# Printing3.net
KiCad netlist of a schematic drawn in Altium Designer
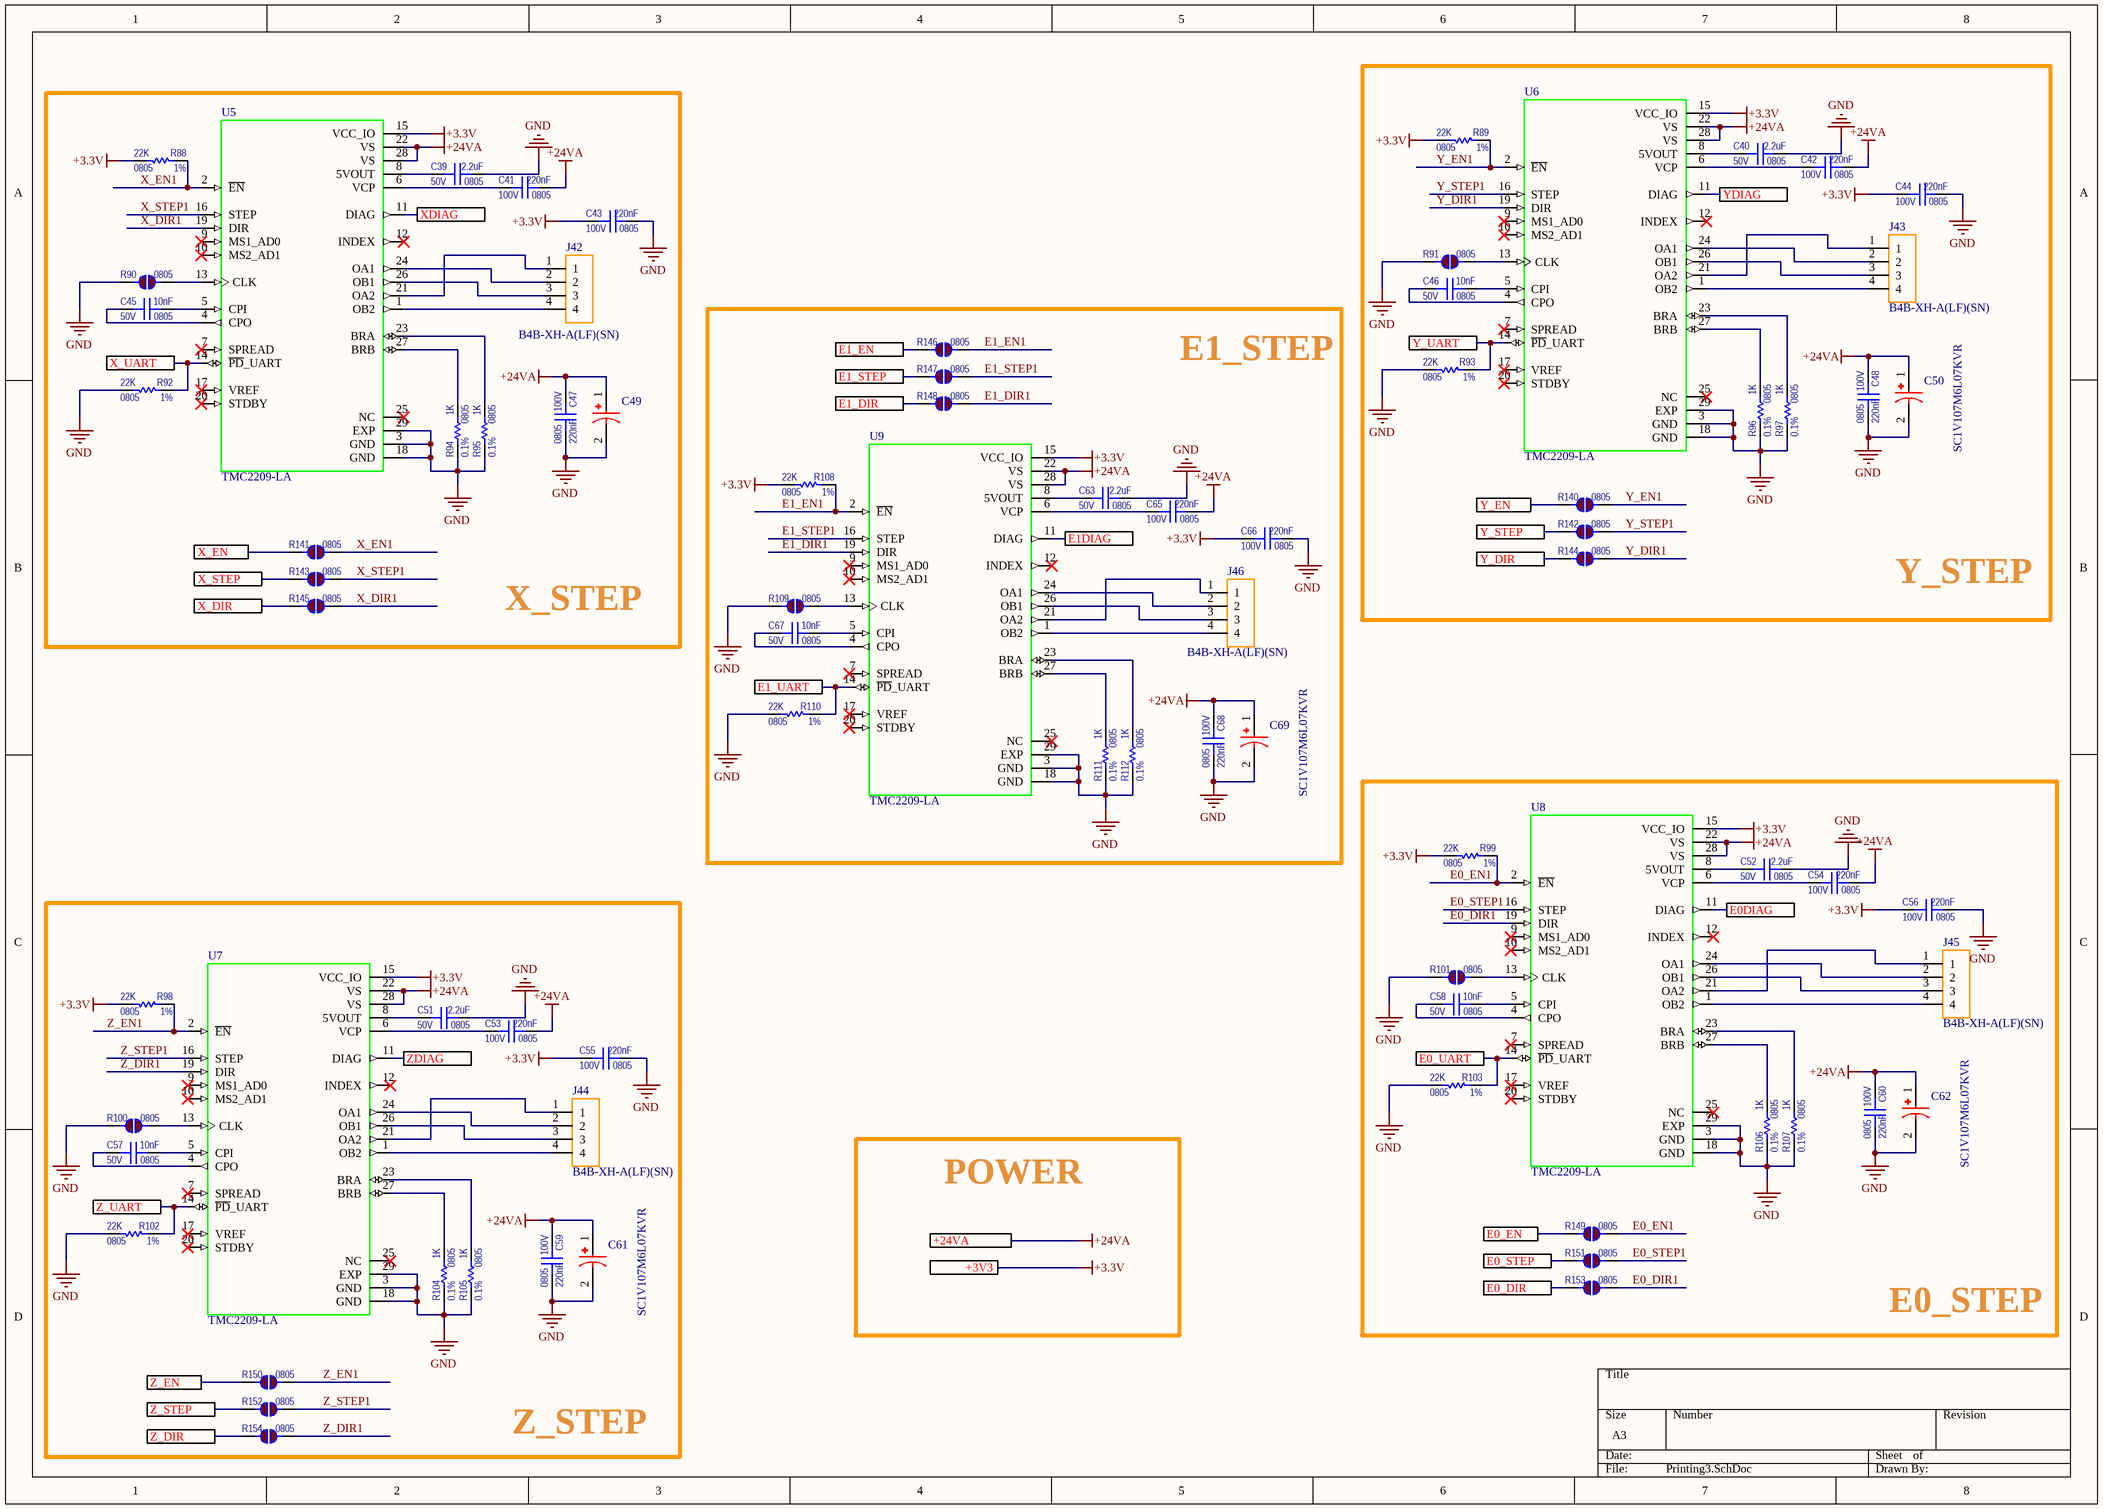
[diagram p0: Printing3.SchDoc]

(export (version "E")
  (design (tool "Eeschema 10.0.6"))
  (components
    (comp (ref "C39")
      (value "2.2uF")
      (footprint "C_0805_GEN_1.40H")
      (description "CAP_CER_2.2uF_16V_X7R_10%_0805")
      (fields
        (field (name "VOLTAGE") "50V")
        (field (name "PACKAGE") "0805")
        (field (name "SIMILAR PART") "CGA4J3X7R1C225K125AB")
        (field (name "TOLERANCE") "10%")
        (field (name "ADDED BY") "SonerI")
        (field (name "CHECKED BY") "İlkerU")
      )
      (libsource (lib "FireANTs_HwLibDB") (part "Capacitor"))
    )
    (comp (ref "C40")
      (value "2.2uF")
      (footprint "C_0805_GEN_1.40H")
      (description "CAP_CER_2.2uF_16V_X7R_10%_0805")
      (fields
        (field (name "VOLTAGE") "50V")
        (field (name "PACKAGE") "0805")
        (field (name "SIMILAR PART") "CGA4J3X7R1C225K125AB")
        (field (name "TOLERANCE") "10%")
        (field (name "ADDED BY") "SonerI")
        (field (name "CHECKED BY") "İlkerU")
      )
      (libsource (lib "FireANTs_HwLibDB") (part "Capacitor"))
    )
    (comp (ref "C41")
      (value "220nF")
      (footprint "C_0805_GEN_1.40H")
      (description "CAP_CER_220nF_100V_X7R_10%_0805")
      (fields
        (field (name "VOLTAGE") "100V")
        (field (name "PACKAGE") "0805")
        (field (name "SIMILAR PART") "CC0805KKX7R0BB224; GRM21AR72A224KAC5L")
        (field (name "TOLERANCE") "10%")
        (field (name "ADDED BY") "YasinY")
        (field (name "CHECKED BY") "İlkerU")
      )
      (libsource (lib "FireANTs_HwLibDB") (part "Capacitor"))
    )
    (comp (ref "C42")
      (value "220nF")
      (footprint "C_0805_GEN_1.40H")
      (description "CAP_CER_220nF_100V_X7R_10%_0805")
      (fields
        (field (name "VOLTAGE") "100V")
        (field (name "PACKAGE") "0805")
        (field (name "SIMILAR PART") "CC0805KKX7R0BB224; GRM21AR72A224KAC5L")
        (field (name "TOLERANCE") "10%")
        (field (name "ADDED BY") "YasinY")
        (field (name "CHECKED BY") "İlkerU")
      )
      (libsource (lib "FireANTs_HwLibDB") (part "Capacitor"))
    )
    (comp (ref "C43")
      (value "220nF")
      (footprint "C_0805_GEN_1.40H")
      (description "CAP_CER_220nF_100V_X7R_10%_0805")
      (fields
        (field (name "VOLTAGE") "100V")
        (field (name "PACKAGE") "0805")
        (field (name "SIMILAR PART") "CC0805KKX7R0BB224; GRM21AR72A224KAC5L")
        (field (name "TOLERANCE") "10%")
        (field (name "ADDED BY") "YasinY")
        (field (name "CHECKED BY") "İlkerU")
      )
      (libsource (lib "FireANTs_HwLibDB") (part "Capacitor"))
    )
    (comp (ref "C44")
      (value "220nF")
      (footprint "C_0805_GEN_1.40H")
      (description "CAP_CER_220nF_100V_X7R_10%_0805")
      (fields
        (field (name "VOLTAGE") "100V")
        (field (name "PACKAGE") "0805")
        (field (name "SIMILAR PART") "CC0805KKX7R0BB224; GRM21AR72A224KAC5L")
        (field (name "TOLERANCE") "10%")
        (field (name "ADDED BY") "YasinY")
        (field (name "CHECKED BY") "İlkerU")
      )
      (libsource (lib "FireANTs_HwLibDB") (part "Capacitor"))
    )
    (comp (ref "C45")
      (value "10nF")
      (footprint "C_0805_GEN_1.10H")
      (description "CAP_CER_10nF_50V_NP0_5%_0805")
      (fields
        (field (name "VOLTAGE") "50V")
        (field (name "PACKAGE") "0805")
        (field (name "SIMILAR PART") "CGA4C2C0G1H103J060AA")
        (field (name "TOLERANCE") "5%")
        (field (name "ADDED BY") "SonerI")
        (field (name "CHECKED BY") "İlkerU")
      )
      (libsource (lib "FireANTs_HwLibDB") (part "Capacitor"))
    )
    (comp (ref "C46")
      (value "10nF")
      (footprint "C_0805_GEN_1.10H")
      (description "CAP_CER_10nF_50V_NP0_5%_0805")
      (fields
        (field (name "VOLTAGE") "50V")
        (field (name "PACKAGE") "0805")
        (field (name "SIMILAR PART") "CGA4C2C0G1H103J060AA")
        (field (name "TOLERANCE") "5%")
        (field (name "ADDED BY") "SonerI")
        (field (name "CHECKED BY") "İlkerU")
      )
      (libsource (lib "FireANTs_HwLibDB") (part "Capacitor"))
    )
    (comp (ref "C47")
      (value "220nF")
      (footprint "C_0805_GEN_1.40H")
      (description "CAP_CER_220nF_100V_X7R_10%_0805")
      (fields
        (field (name "VOLTAGE") "100V")
        (field (name "PACKAGE") "0805")
        (field (name "SIMILAR PART") "CC0805KKX7R0BB224; GRM21AR72A224KAC5L")
        (field (name "TOLERANCE") "10%")
        (field (name "ADDED BY") "YasinY")
        (field (name "CHECKED BY") "İlkerU")
      )
      (libsource (lib "FireANTs_HwLibDB") (part "Capacitor"))
    )
    (comp (ref "C48")
      (value "220nF")
      (footprint "C_0805_GEN_1.40H")
      (description "CAP_CER_220nF_100V_X7R_10%_0805")
      (fields
        (field (name "VOLTAGE") "100V")
        (field (name "PACKAGE") "0805")
        (field (name "SIMILAR PART") "CC0805KKX7R0BB224; GRM21AR72A224KAC5L")
        (field (name "TOLERANCE") "10%")
        (field (name "ADDED BY") "YasinY")
        (field (name "CHECKED BY") "İlkerU")
      )
      (libsource (lib "FireANTs_HwLibDB") (part "Capacitor"))
    )
    (comp (ref "C49")
      (value "SC1V107M6L07KVR")
      (footprint "SC1V107M6L07KVR")
      (libsource (lib "Printing") (part "SC1V107M6L07KVR"))
    )
    (comp (ref "C50")
      (value "SC1V107M6L07KVR")
      (footprint "SC1V107M6L07KVR")
      (libsource (lib "Printing") (part "SC1V107M6L07KVR"))
    )
    (comp (ref "C51")
      (value "2.2uF")
      (footprint "C_0805_GEN_1.40H")
      (description "CAP_CER_2.2uF_16V_X7R_10%_0805")
      (fields
        (field (name "VOLTAGE") "50V")
        (field (name "PACKAGE") "0805")
        (field (name "SIMILAR PART") "CGA4J3X7R1C225K125AB")
        (field (name "TOLERANCE") "10%")
        (field (name "ADDED BY") "SonerI")
        (field (name "CHECKED BY") "İlkerU")
      )
      (libsource (lib "FireANTs_HwLibDB") (part "Capacitor"))
    )
    (comp (ref "C52")
      (value "2.2uF")
      (footprint "C_0805_GEN_1.40H")
      (description "CAP_CER_2.2uF_16V_X7R_10%_0805")
      (fields
        (field (name "VOLTAGE") "50V")
        (field (name "PACKAGE") "0805")
        (field (name "SIMILAR PART") "CGA4J3X7R1C225K125AB")
        (field (name "TOLERANCE") "10%")
        (field (name "ADDED BY") "SonerI")
        (field (name "CHECKED BY") "İlkerU")
      )
      (libsource (lib "FireANTs_HwLibDB") (part "Capacitor"))
    )
    (comp (ref "C53")
      (value "220nF")
      (footprint "C_0805_GEN_1.40H")
      (description "CAP_CER_220nF_100V_X7R_10%_0805")
      (fields
        (field (name "VOLTAGE") "100V")
        (field (name "PACKAGE") "0805")
        (field (name "SIMILAR PART") "CC0805KKX7R0BB224; GRM21AR72A224KAC5L")
        (field (name "TOLERANCE") "10%")
        (field (name "ADDED BY") "YasinY")
        (field (name "CHECKED BY") "İlkerU")
      )
      (libsource (lib "FireANTs_HwLibDB") (part "Capacitor"))
    )
    (comp (ref "C54")
      (value "220nF")
      (footprint "C_0805_GEN_1.40H")
      (description "CAP_CER_220nF_100V_X7R_10%_0805")
      (fields
        (field (name "VOLTAGE") "100V")
        (field (name "PACKAGE") "0805")
        (field (name "SIMILAR PART") "CC0805KKX7R0BB224; GRM21AR72A224KAC5L")
        (field (name "TOLERANCE") "10%")
        (field (name "ADDED BY") "YasinY")
        (field (name "CHECKED BY") "İlkerU")
      )
      (libsource (lib "FireANTs_HwLibDB") (part "Capacitor"))
    )
    (comp (ref "C55")
      (value "220nF")
      (footprint "C_0805_GEN_1.40H")
      (description "CAP_CER_220nF_100V_X7R_10%_0805")
      (fields
        (field (name "VOLTAGE") "100V")
        (field (name "PACKAGE") "0805")
        (field (name "SIMILAR PART") "CC0805KKX7R0BB224; GRM21AR72A224KAC5L")
        (field (name "TOLERANCE") "10%")
        (field (name "ADDED BY") "YasinY")
        (field (name "CHECKED BY") "İlkerU")
      )
      (libsource (lib "FireANTs_HwLibDB") (part "Capacitor"))
    )
    (comp (ref "C56")
      (value "220nF")
      (footprint "C_0805_GEN_1.40H")
      (description "CAP_CER_220nF_100V_X7R_10%_0805")
      (fields
        (field (name "VOLTAGE") "100V")
        (field (name "PACKAGE") "0805")
        (field (name "SIMILAR PART") "CC0805KKX7R0BB224; GRM21AR72A224KAC5L")
        (field (name "TOLERANCE") "10%")
        (field (name "ADDED BY") "YasinY")
        (field (name "CHECKED BY") "İlkerU")
      )
      (libsource (lib "FireANTs_HwLibDB") (part "Capacitor"))
    )
    (comp (ref "C57")
      (value "10nF")
      (footprint "C_0805_GEN_1.10H")
      (description "CAP_CER_10nF_50V_NP0_5%_0805")
      (fields
        (field (name "VOLTAGE") "50V")
        (field (name "PACKAGE") "0805")
        (field (name "SIMILAR PART") "CGA4C2C0G1H103J060AA")
        (field (name "TOLERANCE") "5%")
        (field (name "ADDED BY") "SonerI")
        (field (name "CHECKED BY") "İlkerU")
      )
      (libsource (lib "FireANTs_HwLibDB") (part "Capacitor"))
    )
    (comp (ref "C58")
      (value "10nF")
      (footprint "C_0805_GEN_1.10H")
      (description "CAP_CER_10nF_50V_NP0_5%_0805")
      (fields
        (field (name "VOLTAGE") "50V")
        (field (name "PACKAGE") "0805")
        (field (name "SIMILAR PART") "CGA4C2C0G1H103J060AA")
        (field (name "TOLERANCE") "5%")
        (field (name "ADDED BY") "SonerI")
        (field (name "CHECKED BY") "İlkerU")
      )
      (libsource (lib "FireANTs_HwLibDB") (part "Capacitor"))
    )
    (comp (ref "C59")
      (value "220nF")
      (footprint "C_0805_GEN_1.40H")
      (description "CAP_CER_220nF_100V_X7R_10%_0805")
      (fields
        (field (name "VOLTAGE") "100V")
        (field (name "PACKAGE") "0805")
        (field (name "SIMILAR PART") "CC0805KKX7R0BB224; GRM21AR72A224KAC5L")
        (field (name "TOLERANCE") "10%")
        (field (name "ADDED BY") "YasinY")
        (field (name "CHECKED BY") "İlkerU")
      )
      (libsource (lib "FireANTs_HwLibDB") (part "Capacitor"))
    )
    (comp (ref "C60")
      (value "220nF")
      (footprint "C_0805_GEN_1.40H")
      (description "CAP_CER_220nF_100V_X7R_10%_0805")
      (fields
        (field (name "VOLTAGE") "100V")
        (field (name "PACKAGE") "0805")
        (field (name "SIMILAR PART") "CC0805KKX7R0BB224; GRM21AR72A224KAC5L")
        (field (name "TOLERANCE") "10%")
        (field (name "ADDED BY") "YasinY")
        (field (name "CHECKED BY") "İlkerU")
      )
      (libsource (lib "FireANTs_HwLibDB") (part "Capacitor"))
    )
    (comp (ref "C61")
      (value "SC1V107M6L07KVR")
      (footprint "SC1V107M6L07KVR")
      (libsource (lib "Printing") (part "SC1V107M6L07KVR"))
    )
    (comp (ref "C62")
      (value "SC1V107M6L07KVR")
      (footprint "SC1V107M6L07KVR")
      (libsource (lib "Printing") (part "SC1V107M6L07KVR"))
    )
    (comp (ref "C63")
      (value "2.2uF")
      (footprint "C_0805_GEN_1.40H")
      (description "CAP_CER_2.2uF_16V_X7R_10%_0805")
      (fields
        (field (name "VOLTAGE") "50V")
        (field (name "PACKAGE") "0805")
        (field (name "SIMILAR PART") "CGA4J3X7R1C225K125AB")
        (field (name "TOLERANCE") "10%")
        (field (name "ADDED BY") "SonerI")
        (field (name "CHECKED BY") "İlkerU")
      )
      (libsource (lib "FireANTs_HwLibDB") (part "Capacitor"))
    )
    (comp (ref "C65")
      (value "220nF")
      (footprint "C_0805_GEN_1.40H")
      (description "CAP_CER_220nF_100V_X7R_10%_0805")
      (fields
        (field (name "VOLTAGE") "100V")
        (field (name "PACKAGE") "0805")
        (field (name "SIMILAR PART") "CC0805KKX7R0BB224; GRM21AR72A224KAC5L")
        (field (name "TOLERANCE") "10%")
        (field (name "ADDED BY") "YasinY")
        (field (name "CHECKED BY") "İlkerU")
      )
      (libsource (lib "FireANTs_HwLibDB") (part "Capacitor"))
    )
    (comp (ref "C66")
      (value "220nF")
      (footprint "C_0805_GEN_1.40H")
      (description "CAP_CER_220nF_100V_X7R_10%_0805")
      (fields
        (field (name "VOLTAGE") "100V")
        (field (name "PACKAGE") "0805")
        (field (name "SIMILAR PART") "CC0805KKX7R0BB224; GRM21AR72A224KAC5L")
        (field (name "TOLERANCE") "10%")
        (field (name "ADDED BY") "YasinY")
        (field (name "CHECKED BY") "İlkerU")
      )
      (libsource (lib "FireANTs_HwLibDB") (part "Capacitor"))
    )
    (comp (ref "C67")
      (value "10nF")
      (footprint "C_0805_GEN_1.10H")
      (description "CAP_CER_10nF_50V_NP0_5%_0805")
      (fields
        (field (name "VOLTAGE") "50V")
        (field (name "PACKAGE") "0805")
        (field (name "SIMILAR PART") "CGA4C2C0G1H103J060AA")
        (field (name "TOLERANCE") "5%")
        (field (name "ADDED BY") "SonerI")
        (field (name "CHECKED BY") "İlkerU")
      )
      (libsource (lib "FireANTs_HwLibDB") (part "Capacitor"))
    )
    (comp (ref "C68")
      (value "220nF")
      (footprint "C_0805_GEN_1.40H")
      (description "CAP_CER_220nF_100V_X7R_10%_0805")
      (fields
        (field (name "VOLTAGE") "100V")
        (field (name "PACKAGE") "0805")
        (field (name "SIMILAR PART") "CC0805KKX7R0BB224; GRM21AR72A224KAC5L")
        (field (name "TOLERANCE") "10%")
        (field (name "ADDED BY") "YasinY")
        (field (name "CHECKED BY") "İlkerU")
      )
      (libsource (lib "FireANTs_HwLibDB") (part "Capacitor"))
    )
    (comp (ref "C69")
      (value "SC1V107M6L07KVR")
      (footprint "SC1V107M6L07KVR")
      (libsource (lib "Printing") (part "SC1V107M6L07KVR"))
    )
    (comp (ref "J42")
      (value "B4B-XH-A(LF)(SN)")
      (footprint "JST_B4B-XH-A(LF)(SN)")
      (libsource (lib "Printing") (part "B4B-XH-A(LF)(SN)"))
    )
    (comp (ref "J43")
      (value "B4B-XH-A(LF)(SN)")
      (footprint "JST_B4B-XH-A(LF)(SN)")
      (libsource (lib "Printing") (part "B4B-XH-A(LF)(SN)"))
    )
    (comp (ref "J44")
      (value "B4B-XH-A(LF)(SN)")
      (footprint "JST_B4B-XH-A(LF)(SN)")
      (libsource (lib "Printing") (part "B4B-XH-A(LF)(SN)"))
    )
    (comp (ref "J45")
      (value "B4B-XH-A(LF)(SN)")
      (footprint "JST_B4B-XH-A(LF)(SN)")
      (libsource (lib "Printing") (part "B4B-XH-A(LF)(SN)"))
    )
    (comp (ref "J46")
      (value "B4B-XH-A(LF)(SN)")
      (footprint "JST_B4B-XH-A(LF)(SN)")
      (libsource (lib "Printing") (part "B4B-XH-A(LF)(SN)"))
    )
    (comp (ref "R88")
      (value "22K")
      (footprint "R_0805_GEN_0.70H")
      (description "RES_STD_22K_0.125W_1%_100ppm_0805")
      (fields
        (field (name "TOLERANCE") "1%")
        (field (name "PACKAGE") "0805")
        (field (name "VOLTAGE") "150V")
        (field (name "Comment") "StandardResistor")
        (field (name "ADDED BY") "SonerI")
        (field (name "CHECKED BY") "YasinY")
      )
      (libsource (lib "FireANTs_HwLibDB") (part "StandardResistor"))
    )
    (comp (ref "R89")
      (value "22K")
      (footprint "R_0805_GEN_0.70H")
      (description "RES_STD_22K_0.125W_1%_100ppm_0805")
      (fields
        (field (name "TOLERANCE") "1%")
        (field (name "PACKAGE") "0805")
        (field (name "VOLTAGE") "150V")
        (field (name "Comment") "StandardResistor")
        (field (name "ADDED BY") "SonerI")
        (field (name "CHECKED BY") "YasinY")
      )
      (libsource (lib "FireANTs_HwLibDB") (part "StandardResistor"))
    )
    (comp (ref "R90")
      (value "StandardJumper")
      (footprint "R_0805_GEN_0.70H")
      (description "RES_STD_0R_0.125W_0805")
      (fields
        (field (name "PACKAGE") "0805")
        (field (name "TOLERANCE") "5%")
        (field (name "VOLTAGE") "150V")
        (field (name "ADDED BY") "İlhanT")
        (field (name "CHECKED BY") "YasinY")
      )
      (libsource (lib "FireANTs_HwLibDB") (part "StandardJumper"))
    )
    (comp (ref "R91")
      (value "StandardJumper")
      (footprint "R_0805_GEN_0.70H")
      (description "RES_STD_0R_0.125W_0805")
      (fields
        (field (name "PACKAGE") "0805")
        (field (name "TOLERANCE") "5%")
        (field (name "VOLTAGE") "150V")
        (field (name "ADDED BY") "İlhanT")
        (field (name "CHECKED BY") "YasinY")
      )
      (libsource (lib "FireANTs_HwLibDB") (part "StandardJumper"))
    )
    (comp (ref "R92")
      (value "22K")
      (footprint "R_0805_GEN_0.70H")
      (description "RES_STD_22K_0.125W_1%_100ppm_0805")
      (fields
        (field (name "TOLERANCE") "1%")
        (field (name "PACKAGE") "0805")
        (field (name "VOLTAGE") "150V")
        (field (name "Comment") "StandardResistor")
        (field (name "ADDED BY") "SonerI")
        (field (name "CHECKED BY") "YasinY")
      )
      (libsource (lib "FireANTs_HwLibDB") (part "StandardResistor"))
    )
    (comp (ref "R93")
      (value "22K")
      (footprint "R_0805_GEN_0.70H")
      (description "RES_STD_22K_0.125W_1%_100ppm_0805")
      (fields
        (field (name "TOLERANCE") "1%")
        (field (name "PACKAGE") "0805")
        (field (name "VOLTAGE") "150V")
        (field (name "Comment") "StandardResistor")
        (field (name "ADDED BY") "SonerI")
        (field (name "CHECKED BY") "YasinY")
      )
      (libsource (lib "FireANTs_HwLibDB") (part "StandardResistor"))
    )
    (comp (ref "R94")
      (value "1K")
      (footprint "R_0805_GEN_0.70H")
      (description "RES_STD_1K_0.125W_0.1%_25ppm_0805")
      (fields
        (field (name "TOLERANCE") "0.1%")
        (field (name "PACKAGE") "0805")
        (field (name "SIMILAR PART") "RN73C2A1K0BTD")
        (field (name "VOLTAGE") "100V")
        (field (name "ADDED BY") "İlhanT")
        (field (name "CHECKED BY") "YasinY")
      )
      (libsource (lib "FireANTs_HwLibDB") (part "StandardResistor"))
    )
    (comp (ref "R95")
      (value "1K")
      (footprint "R_0805_GEN_0.70H")
      (description "RES_STD_1K_0.125W_0.1%_25ppm_0805")
      (fields
        (field (name "TOLERANCE") "0.1%")
        (field (name "PACKAGE") "0805")
        (field (name "SIMILAR PART") "RN73C2A1K0BTD")
        (field (name "VOLTAGE") "100V")
        (field (name "ADDED BY") "İlhanT")
        (field (name "CHECKED BY") "YasinY")
      )
      (libsource (lib "FireANTs_HwLibDB") (part "StandardResistor"))
    )
    (comp (ref "R96")
      (value "1K")
      (footprint "R_0805_GEN_0.70H")
      (description "RES_STD_1K_0.125W_0.1%_25ppm_0805")
      (fields
        (field (name "TOLERANCE") "0.1%")
        (field (name "PACKAGE") "0805")
        (field (name "SIMILAR PART") "RN73C2A1K0BTD")
        (field (name "VOLTAGE") "100V")
        (field (name "ADDED BY") "İlhanT")
        (field (name "CHECKED BY") "YasinY")
      )
      (libsource (lib "FireANTs_HwLibDB") (part "StandardResistor"))
    )
    (comp (ref "R97")
      (value "1K")
      (footprint "R_0805_GEN_0.70H")
      (description "RES_STD_1K_0.125W_0.1%_25ppm_0805")
      (fields
        (field (name "TOLERANCE") "0.1%")
        (field (name "PACKAGE") "0805")
        (field (name "SIMILAR PART") "RN73C2A1K0BTD")
        (field (name "VOLTAGE") "100V")
        (field (name "ADDED BY") "İlhanT")
        (field (name "CHECKED BY") "YasinY")
      )
      (libsource (lib "FireANTs_HwLibDB") (part "StandardResistor"))
    )
    (comp (ref "R98")
      (value "22K")
      (footprint "R_0805_GEN_0.70H")
      (description "RES_STD_22K_0.125W_1%_100ppm_0805")
      (fields
        (field (name "TOLERANCE") "1%")
        (field (name "PACKAGE") "0805")
        (field (name "VOLTAGE") "150V")
        (field (name "Comment") "StandardResistor")
        (field (name "ADDED BY") "SonerI")
        (field (name "CHECKED BY") "YasinY")
      )
      (libsource (lib "FireANTs_HwLibDB") (part "StandardResistor"))
    )
    (comp (ref "R99")
      (value "22K")
      (footprint "R_0805_GEN_0.70H")
      (description "RES_STD_22K_0.125W_1%_100ppm_0805")
      (fields
        (field (name "TOLERANCE") "1%")
        (field (name "PACKAGE") "0805")
        (field (name "VOLTAGE") "150V")
        (field (name "Comment") "StandardResistor")
        (field (name "ADDED BY") "SonerI")
        (field (name "CHECKED BY") "YasinY")
      )
      (libsource (lib "FireANTs_HwLibDB") (part "StandardResistor"))
    )
    (comp (ref "R100")
      (value "StandardJumper")
      (footprint "R_0805_GEN_0.70H")
      (description "RES_STD_0R_0.125W_0805")
      (fields
        (field (name "PACKAGE") "0805")
        (field (name "TOLERANCE") "5%")
        (field (name "VOLTAGE") "150V")
        (field (name "ADDED BY") "İlhanT")
        (field (name "CHECKED BY") "YasinY")
      )
      (libsource (lib "FireANTs_HwLibDB") (part "StandardJumper"))
    )
    (comp (ref "R101")
      (value "StandardJumper")
      (footprint "R_0805_GEN_0.70H")
      (description "RES_STD_0R_0.125W_0805")
      (fields
        (field (name "PACKAGE") "0805")
        (field (name "TOLERANCE") "5%")
        (field (name "VOLTAGE") "150V")
        (field (name "ADDED BY") "İlhanT")
        (field (name "CHECKED BY") "YasinY")
      )
      (libsource (lib "FireANTs_HwLibDB") (part "StandardJumper"))
    )
    (comp (ref "R102")
      (value "22K")
      (footprint "R_0805_GEN_0.70H")
      (description "RES_STD_22K_0.125W_1%_100ppm_0805")
      (fields
        (field (name "TOLERANCE") "1%")
        (field (name "PACKAGE") "0805")
        (field (name "VOLTAGE") "150V")
        (field (name "Comment") "StandardResistor")
        (field (name "ADDED BY") "SonerI")
        (field (name "CHECKED BY") "YasinY")
      )
      (libsource (lib "FireANTs_HwLibDB") (part "StandardResistor"))
    )
    (comp (ref "R103")
      (value "22K")
      (footprint "R_0805_GEN_0.70H")
      (description "RES_STD_22K_0.125W_1%_100ppm_0805")
      (fields
        (field (name "TOLERANCE") "1%")
        (field (name "PACKAGE") "0805")
        (field (name "VOLTAGE") "150V")
        (field (name "Comment") "StandardResistor")
        (field (name "ADDED BY") "SonerI")
        (field (name "CHECKED BY") "YasinY")
      )
      (libsource (lib "FireANTs_HwLibDB") (part "StandardResistor"))
    )
    (comp (ref "R104")
      (value "1K")
      (footprint "R_0805_GEN_0.70H")
      (description "RES_STD_1K_0.125W_0.1%_25ppm_0805")
      (fields
        (field (name "TOLERANCE") "0.1%")
        (field (name "PACKAGE") "0805")
        (field (name "SIMILAR PART") "RN73C2A1K0BTD")
        (field (name "VOLTAGE") "100V")
        (field (name "ADDED BY") "İlhanT")
        (field (name "CHECKED BY") "YasinY")
      )
      (libsource (lib "FireANTs_HwLibDB") (part "StandardResistor"))
    )
    (comp (ref "R105")
      (value "1K")
      (footprint "R_0805_GEN_0.70H")
      (description "RES_STD_1K_0.125W_0.1%_25ppm_0805")
      (fields
        (field (name "TOLERANCE") "0.1%")
        (field (name "PACKAGE") "0805")
        (field (name "SIMILAR PART") "RN73C2A1K0BTD")
        (field (name "VOLTAGE") "100V")
        (field (name "ADDED BY") "İlhanT")
        (field (name "CHECKED BY") "YasinY")
      )
      (libsource (lib "FireANTs_HwLibDB") (part "StandardResistor"))
    )
    (comp (ref "R106")
      (value "1K")
      (footprint "R_0805_GEN_0.70H")
      (description "RES_STD_1K_0.125W_0.1%_25ppm_0805")
      (fields
        (field (name "TOLERANCE") "0.1%")
        (field (name "PACKAGE") "0805")
        (field (name "SIMILAR PART") "RN73C2A1K0BTD")
        (field (name "VOLTAGE") "100V")
        (field (name "ADDED BY") "İlhanT")
        (field (name "CHECKED BY") "YasinY")
      )
      (libsource (lib "FireANTs_HwLibDB") (part "StandardResistor"))
    )
    (comp (ref "R107")
      (value "1K")
      (footprint "R_0805_GEN_0.70H")
      (description "RES_STD_1K_0.125W_0.1%_25ppm_0805")
      (fields
        (field (name "TOLERANCE") "0.1%")
        (field (name "PACKAGE") "0805")
        (field (name "SIMILAR PART") "RN73C2A1K0BTD")
        (field (name "VOLTAGE") "100V")
        (field (name "ADDED BY") "İlhanT")
        (field (name "CHECKED BY") "YasinY")
      )
      (libsource (lib "FireANTs_HwLibDB") (part "StandardResistor"))
    )
    (comp (ref "R108")
      (value "22K")
      (footprint "R_0805_GEN_0.70H")
      (description "RES_STD_22K_0.125W_1%_100ppm_0805")
      (fields
        (field (name "TOLERANCE") "1%")
        (field (name "PACKAGE") "0805")
        (field (name "VOLTAGE") "150V")
        (field (name "Comment") "StandardResistor")
        (field (name "ADDED BY") "SonerI")
        (field (name "CHECKED BY") "YasinY")
      )
      (libsource (lib "FireANTs_HwLibDB") (part "StandardResistor"))
    )
    (comp (ref "R109")
      (value "StandardJumper")
      (footprint "R_0805_GEN_0.70H")
      (description "RES_STD_0R_0.125W_0805")
      (fields
        (field (name "PACKAGE") "0805")
        (field (name "TOLERANCE") "5%")
        (field (name "VOLTAGE") "150V")
        (field (name "ADDED BY") "İlhanT")
        (field (name "CHECKED BY") "YasinY")
      )
      (libsource (lib "FireANTs_HwLibDB") (part "StandardJumper"))
    )
    (comp (ref "R110")
      (value "22K")
      (footprint "R_0805_GEN_0.70H")
      (description "RES_STD_22K_0.125W_1%_100ppm_0805")
      (fields
        (field (name "TOLERANCE") "1%")
        (field (name "PACKAGE") "0805")
        (field (name "VOLTAGE") "150V")
        (field (name "Comment") "StandardResistor")
        (field (name "ADDED BY") "SonerI")
        (field (name "CHECKED BY") "YasinY")
      )
      (libsource (lib "FireANTs_HwLibDB") (part "StandardResistor"))
    )
    (comp (ref "R111")
      (value "1K")
      (footprint "R_0805_GEN_0.70H")
      (description "RES_STD_1K_0.125W_0.1%_25ppm_0805")
      (fields
        (field (name "TOLERANCE") "0.1%")
        (field (name "PACKAGE") "0805")
        (field (name "SIMILAR PART") "RN73C2A1K0BTD")
        (field (name "VOLTAGE") "100V")
        (field (name "ADDED BY") "İlhanT")
        (field (name "CHECKED BY") "YasinY")
      )
      (libsource (lib "FireANTs_HwLibDB") (part "StandardResistor"))
    )
    (comp (ref "R112")
      (value "1K")
      (footprint "R_0805_GEN_0.70H")
      (description "RES_STD_1K_0.125W_0.1%_25ppm_0805")
      (fields
        (field (name "TOLERANCE") "0.1%")
        (field (name "PACKAGE") "0805")
        (field (name "SIMILAR PART") "RN73C2A1K0BTD")
        (field (name "VOLTAGE") "100V")
        (field (name "ADDED BY") "İlhanT")
        (field (name "CHECKED BY") "YasinY")
      )
      (libsource (lib "FireANTs_HwLibDB") (part "StandardResistor"))
    )
    (comp (ref "R140")
      (value "StandardJumper")
      (footprint "R_0805_GEN_0.70H")
      (description "RES_STD_0R_0.125W_0805")
      (fields
        (field (name "PACKAGE") "0805")
        (field (name "TOLERANCE") "5%")
        (field (name "VOLTAGE") "150V")
        (field (name "ADDED BY") "İlhanT")
        (field (name "CHECKED BY") "YasinY")
      )
      (libsource (lib "FireANTs_HwLibDB") (part "StandardJumper"))
    )
    (comp (ref "R141")
      (value "StandardJumper")
      (footprint "R_0805_GEN_0.70H")
      (description "RES_STD_0R_0.125W_0805")
      (fields
        (field (name "PACKAGE") "0805")
        (field (name "TOLERANCE") "5%")
        (field (name "VOLTAGE") "150V")
        (field (name "ADDED BY") "İlhanT")
        (field (name "CHECKED BY") "YasinY")
      )
      (libsource (lib "FireANTs_HwLibDB") (part "StandardJumper"))
    )
    (comp (ref "R142")
      (value "StandardJumper")
      (footprint "R_0805_GEN_0.70H")
      (description "RES_STD_0R_0.125W_0805")
      (fields
        (field (name "PACKAGE") "0805")
        (field (name "TOLERANCE") "5%")
        (field (name "VOLTAGE") "150V")
        (field (name "ADDED BY") "İlhanT")
        (field (name "CHECKED BY") "YasinY")
      )
      (libsource (lib "FireANTs_HwLibDB") (part "StandardJumper"))
    )
    (comp (ref "R143")
      (value "StandardJumper")
      (footprint "R_0805_GEN_0.70H")
      (description "RES_STD_0R_0.125W_0805")
      (fields
        (field (name "PACKAGE") "0805")
        (field (name "TOLERANCE") "5%")
        (field (name "VOLTAGE") "150V")
        (field (name "ADDED BY") "İlhanT")
        (field (name "CHECKED BY") "YasinY")
      )
      (libsource (lib "FireANTs_HwLibDB") (part "StandardJumper"))
    )
    (comp (ref "R144")
      (value "StandardJumper")
      (footprint "R_0805_GEN_0.70H")
      (description "RES_STD_0R_0.125W_0805")
      (fields
        (field (name "PACKAGE") "0805")
        (field (name "TOLERANCE") "5%")
        (field (name "VOLTAGE") "150V")
        (field (name "ADDED BY") "İlhanT")
        (field (name "CHECKED BY") "YasinY")
      )
      (libsource (lib "FireANTs_HwLibDB") (part "StandardJumper"))
    )
    (comp (ref "R145")
      (value "StandardJumper")
      (footprint "R_0805_GEN_0.70H")
      (description "RES_STD_0R_0.125W_0805")
      (fields
        (field (name "PACKAGE") "0805")
        (field (name "TOLERANCE") "5%")
        (field (name "VOLTAGE") "150V")
        (field (name "ADDED BY") "İlhanT")
        (field (name "CHECKED BY") "YasinY")
      )
      (libsource (lib "FireANTs_HwLibDB") (part "StandardJumper"))
    )
    (comp (ref "R146")
      (value "StandardJumper")
      (footprint "R_0805_GEN_0.70H")
      (description "RES_STD_0R_0.125W_0805")
      (fields
        (field (name "PACKAGE") "0805")
        (field (name "TOLERANCE") "5%")
        (field (name "VOLTAGE") "150V")
        (field (name "ADDED BY") "İlhanT")
        (field (name "CHECKED BY") "YasinY")
      )
      (libsource (lib "FireANTs_HwLibDB") (part "StandardJumper"))
    )
    (comp (ref "R147")
      (value "StandardJumper")
      (footprint "R_0805_GEN_0.70H")
      (description "RES_STD_0R_0.125W_0805")
      (fields
        (field (name "PACKAGE") "0805")
        (field (name "TOLERANCE") "5%")
        (field (name "VOLTAGE") "150V")
        (field (name "ADDED BY") "İlhanT")
        (field (name "CHECKED BY") "YasinY")
      )
      (libsource (lib "FireANTs_HwLibDB") (part "StandardJumper"))
    )
    (comp (ref "R148")
      (value "StandardJumper")
      (footprint "R_0805_GEN_0.70H")
      (description "RES_STD_0R_0.125W_0805")
      (fields
        (field (name "PACKAGE") "0805")
        (field (name "TOLERANCE") "5%")
        (field (name "VOLTAGE") "150V")
        (field (name "ADDED BY") "İlhanT")
        (field (name "CHECKED BY") "YasinY")
      )
      (libsource (lib "FireANTs_HwLibDB") (part "StandardJumper"))
    )
    (comp (ref "R149")
      (value "StandardJumper")
      (footprint "R_0805_GEN_0.70H")
      (description "RES_STD_0R_0.125W_0805")
      (fields
        (field (name "PACKAGE") "0805")
        (field (name "TOLERANCE") "5%")
        (field (name "VOLTAGE") "150V")
        (field (name "ADDED BY") "İlhanT")
        (field (name "CHECKED BY") "YasinY")
      )
      (libsource (lib "FireANTs_HwLibDB") (part "StandardJumper"))
    )
    (comp (ref "R150")
      (value "StandardJumper")
      (footprint "R_0805_GEN_0.70H")
      (description "RES_STD_0R_0.125W_0805")
      (fields
        (field (name "PACKAGE") "0805")
        (field (name "TOLERANCE") "5%")
        (field (name "VOLTAGE") "150V")
        (field (name "ADDED BY") "İlhanT")
        (field (name "CHECKED BY") "YasinY")
      )
      (libsource (lib "FireANTs_HwLibDB") (part "StandardJumper"))
    )
    (comp (ref "R151")
      (value "StandardJumper")
      (footprint "R_0805_GEN_0.70H")
      (description "RES_STD_0R_0.125W_0805")
      (fields
        (field (name "PACKAGE") "0805")
        (field (name "TOLERANCE") "5%")
        (field (name "VOLTAGE") "150V")
        (field (name "ADDED BY") "İlhanT")
        (field (name "CHECKED BY") "YasinY")
      )
      (libsource (lib "FireANTs_HwLibDB") (part "StandardJumper"))
    )
    (comp (ref "R152")
      (value "StandardJumper")
      (footprint "R_0805_GEN_0.70H")
      (description "RES_STD_0R_0.125W_0805")
      (fields
        (field (name "PACKAGE") "0805")
        (field (name "TOLERANCE") "5%")
        (field (name "VOLTAGE") "150V")
        (field (name "ADDED BY") "İlhanT")
        (field (name "CHECKED BY") "YasinY")
      )
      (libsource (lib "FireANTs_HwLibDB") (part "StandardJumper"))
    )
    (comp (ref "R153")
      (value "StandardJumper")
      (footprint "R_0805_GEN_0.70H")
      (description "RES_STD_0R_0.125W_0805")
      (fields
        (field (name "PACKAGE") "0805")
        (field (name "TOLERANCE") "5%")
        (field (name "VOLTAGE") "150V")
        (field (name "ADDED BY") "İlhanT")
        (field (name "CHECKED BY") "YasinY")
      )
      (libsource (lib "FireANTs_HwLibDB") (part "StandardJumper"))
    )
    (comp (ref "R154")
      (value "StandardJumper")
      (footprint "R_0805_GEN_0.70H")
      (description "RES_STD_0R_0.125W_0805")
      (fields
        (field (name "PACKAGE") "0805")
        (field (name "TOLERANCE") "5%")
        (field (name "VOLTAGE") "150V")
        (field (name "ADDED BY") "İlhanT")
        (field (name "CHECKED BY") "YasinY")
      )
      (libsource (lib "FireANTs_HwLibDB") (part "StandardJumper"))
    )
    (comp (ref "U5")
      (value "TMC2209-LA")
      (footprint "QFN50P500X500X90-29N")
      (fields (field (name "MF") "Trinamic"))
      (libsource (lib "Printing") (part "TMC2209-LA"))
    )
    (comp (ref "U6")
      (value "TMC2209-LA")
      (footprint "QFN50P500X500X90-29N")
      (fields (field (name "MF") "Trinamic"))
      (libsource (lib "Printing") (part "TMC2209-LA"))
    )
    (comp (ref "U7")
      (value "TMC2209-LA")
      (footprint "QFN50P500X500X90-29N")
      (fields (field (name "MF") "Trinamic"))
      (libsource (lib "Printing") (part "TMC2209-LA"))
    )
    (comp (ref "U8")
      (value "TMC2209-LA")
      (footprint "QFN50P500X500X90-29N")
      (fields (field (name "MF") "Trinamic"))
      (libsource (lib "Printing") (part "TMC2209-LA"))
    )
    (comp (ref "U9")
      (value "TMC2209-LA")
      (footprint "QFN50P500X500X90-29N")
      (fields (field (name "MF") "Trinamic"))
      (libsource (lib "Printing") (part "TMC2209-LA"))
    )
  )
  (nets
    (net (code "1") (name "+3.3V") (class "Default")
      (node (ref "C43") (pin "1") (pinfunction "1_1") (pintype "passive"))
      (node (ref "C44") (pin "1") (pinfunction "1_1") (pintype "passive"))
      (node (ref "C55") (pin "1") (pinfunction "1_1") (pintype "passive"))
      (node (ref "C56") (pin "1") (pinfunction "1_1") (pintype "passive"))
      (node (ref "C66") (pin "1") (pinfunction "1_1") (pintype "passive"))
      (node (ref "R108") (pin "2") (pinfunction "2_2") (pintype "passive"))
      (node (ref "R88") (pin "2") (pinfunction "2_2") (pintype "passive"))
      (node (ref "R89") (pin "2") (pinfunction "2_2") (pintype "passive"))
      (node (ref "R98") (pin "2") (pinfunction "2_2") (pintype "passive"))
      (node (ref "R99") (pin "2") (pinfunction "2_2") (pintype "passive"))
      (node (ref "U5") (pin "15") (pinfunction "VCC_IO_15") (pintype "power_in"))
      (node (ref "U6") (pin "15") (pinfunction "VCC_IO_15") (pintype "power_in"))
      (node (ref "U7") (pin "15") (pinfunction "VCC_IO_15") (pintype "power_in"))
      (node (ref "U8") (pin "15") (pinfunction "VCC_IO_15") (pintype "power_in"))
      (node (ref "U9") (pin "15") (pinfunction "VCC_IO_15") (pintype "power_in"))
    )
    (net (code "2") (name "+24VA") (class "Default")
      (node (ref "C41") (pin "2") (pinfunction "2_2") (pintype "passive"))
      (node (ref "C42") (pin "2") (pinfunction "2_2") (pintype "passive"))
      (node (ref "C47") (pin "1") (pinfunction "1_1") (pintype "passive"))
      (node (ref "C48") (pin "1") (pinfunction "1_1") (pintype "passive"))
      (node (ref "C49") (pin "1") (pinfunction "1_1") (pintype "passive"))
      (node (ref "C50") (pin "1") (pinfunction "1_1") (pintype "passive"))
      (node (ref "C53") (pin "2") (pinfunction "2_2") (pintype "passive"))
      (node (ref "C54") (pin "2") (pinfunction "2_2") (pintype "passive"))
      (node (ref "C59") (pin "1") (pinfunction "1_1") (pintype "passive"))
      (node (ref "C60") (pin "1") (pinfunction "1_1") (pintype "passive"))
      (node (ref "C61") (pin "1") (pinfunction "1_1") (pintype "passive"))
      (node (ref "C62") (pin "1") (pinfunction "1_1") (pintype "passive"))
      (node (ref "C65") (pin "2") (pinfunction "2_2") (pintype "passive"))
      (node (ref "C68") (pin "1") (pinfunction "1_1") (pintype "passive"))
      (node (ref "C69") (pin "1") (pinfunction "1_1") (pintype "passive"))
      (node (ref "U5") (pin "22") (pinfunction "VS_22") (pintype "power_in"))
      (node (ref "U5") (pin "28") (pinfunction "VS_28") (pintype "power_in"))
      (node (ref "U6") (pin "22") (pinfunction "VS_22") (pintype "power_in"))
      (node (ref "U6") (pin "28") (pinfunction "VS_28") (pintype "power_in"))
      (node (ref "U7") (pin "22") (pinfunction "VS_22") (pintype "power_in"))
      (node (ref "U7") (pin "28") (pinfunction "VS_28") (pintype "power_in"))
      (node (ref "U8") (pin "22") (pinfunction "VS_22") (pintype "power_in"))
      (node (ref "U8") (pin "28") (pinfunction "VS_28") (pintype "power_in"))
      (node (ref "U9") (pin "22") (pinfunction "VS_22") (pintype "power_in"))
      (node (ref "U9") (pin "28") (pinfunction "VS_28") (pintype "power_in"))
    )
    (net (code "3") (name "/E0DIAG") (class "Default")
      (node (ref "U8") (pin "11") (pinfunction "DIAG_11") (pintype "output"))
    )
    (net (code "4") (name "/E0_DIR") (class "Default")
      (node (ref "R153") (pin "1") (pinfunction "1_1") (pintype "passive"))
    )
    (net (code "5") (name "/E0_DIR1") (class "Default")
      (node (ref "R153") (pin "2") (pinfunction "2_2") (pintype "passive"))
      (node (ref "U8") (pin "19") (pinfunction "DIR_19") (pintype "input"))
    )
    (net (code "6") (name "/E0_EN") (class "Default")
      (node (ref "R149") (pin "1") (pinfunction "1_1") (pintype "passive"))
    )
    (net (code "7") (name "/E0_EN1") (class "Default")
      (node (ref "R149") (pin "2") (pinfunction "2_2") (pintype "passive"))
      (node (ref "R99") (pin "1") (pinfunction "1_1") (pintype "passive"))
      (node (ref "U8") (pin "2") (pinfunction "~{EN}_2") (pintype "input"))
    )
    (net (code "8") (name "/E0_STEP") (class "Default")
      (node (ref "R151") (pin "1") (pinfunction "1_1") (pintype "passive"))
    )
    (net (code "9") (name "/E0_STEP1") (class "Default")
      (node (ref "R151") (pin "2") (pinfunction "2_2") (pintype "passive"))
      (node (ref "U8") (pin "16") (pinfunction "STEP_16") (pintype "input"))
    )
    (net (code "10") (name "/E0_UART") (class "Default")
      (node (ref "R103") (pin "1") (pinfunction "1_1") (pintype "passive"))
      (node (ref "U8") (pin "14") (pinfunction "~{PD}_UART_14") (pintype "bidirectional"))
    )
    (net (code "11") (name "/E1DIAG") (class "Default")
      (node (ref "U9") (pin "11") (pinfunction "DIAG_11") (pintype "output"))
    )
    (net (code "12") (name "/E1_DIR") (class "Default")
      (node (ref "R148") (pin "1") (pinfunction "1_1") (pintype "passive"))
    )
    (net (code "13") (name "/E1_DIR1") (class "Default")
      (node (ref "R148") (pin "2") (pinfunction "2_2") (pintype "passive"))
      (node (ref "U9") (pin "19") (pinfunction "DIR_19") (pintype "input"))
    )
    (net (code "14") (name "/E1_EN") (class "Default")
      (node (ref "R146") (pin "1") (pinfunction "1_1") (pintype "passive"))
    )
    (net (code "15") (name "/E1_EN1") (class "Default")
      (node (ref "R108") (pin "1") (pinfunction "1_1") (pintype "passive"))
      (node (ref "R146") (pin "2") (pinfunction "2_2") (pintype "passive"))
      (node (ref "U9") (pin "2") (pinfunction "~{EN}_2") (pintype "input"))
    )
    (net (code "16") (name "/E1_STEP") (class "Default")
      (node (ref "R147") (pin "1") (pinfunction "1_1") (pintype "passive"))
    )
    (net (code "17") (name "/E1_STEP1") (class "Default")
      (node (ref "R147") (pin "2") (pinfunction "2_2") (pintype "passive"))
      (node (ref "U9") (pin "16") (pinfunction "STEP_16") (pintype "input"))
    )
    (net (code "18") (name "/E1_UART") (class "Default")
      (node (ref "R110") (pin "1") (pinfunction "1_1") (pintype "passive"))
      (node (ref "U9") (pin "14") (pinfunction "~{PD}_UART_14") (pintype "bidirectional"))
    )
    (net (code "19") (name "/XDIAG") (class "Default")
      (node (ref "U5") (pin "11") (pinfunction "DIAG_11") (pintype "output"))
    )
    (net (code "20") (name "/X_DIR") (class "Default")
      (node (ref "R145") (pin "1") (pinfunction "1_1") (pintype "passive"))
    )
    (net (code "21") (name "/X_DIR1") (class "Default")
      (node (ref "R145") (pin "2") (pinfunction "2_2") (pintype "passive"))
      (node (ref "U5") (pin "19") (pinfunction "DIR_19") (pintype "input"))
    )
    (net (code "22") (name "/X_EN") (class "Default")
      (node (ref "R141") (pin "1") (pinfunction "1_1") (pintype "passive"))
    )
    (net (code "23") (name "/X_EN1") (class "Default")
      (node (ref "R141") (pin "2") (pinfunction "2_2") (pintype "passive"))
      (node (ref "R88") (pin "1") (pinfunction "1_1") (pintype "passive"))
      (node (ref "U5") (pin "2") (pinfunction "~{EN}_2") (pintype "input"))
    )
    (net (code "24") (name "/X_STEP") (class "Default")
      (node (ref "R143") (pin "1") (pinfunction "1_1") (pintype "passive"))
    )
    (net (code "25") (name "/X_STEP1") (class "Default")
      (node (ref "R143") (pin "2") (pinfunction "2_2") (pintype "passive"))
      (node (ref "U5") (pin "16") (pinfunction "STEP_16") (pintype "input"))
    )
    (net (code "26") (name "/X_UART") (class "Default")
      (node (ref "R92") (pin "1") (pinfunction "1_1") (pintype "passive"))
      (node (ref "U5") (pin "14") (pinfunction "~{PD}_UART_14") (pintype "bidirectional"))
    )
    (net (code "27") (name "/YDIAG") (class "Default")
      (node (ref "U6") (pin "11") (pinfunction "DIAG_11") (pintype "output"))
    )
    (net (code "28") (name "/Y_DIR") (class "Default")
      (node (ref "R144") (pin "1") (pinfunction "1_1") (pintype "passive"))
    )
    (net (code "29") (name "/Y_DIR1") (class "Default")
      (node (ref "R144") (pin "2") (pinfunction "2_2") (pintype "passive"))
      (node (ref "U6") (pin "19") (pinfunction "DIR_19") (pintype "input"))
    )
    (net (code "30") (name "/Y_EN") (class "Default")
      (node (ref "R140") (pin "1") (pinfunction "1_1") (pintype "passive"))
    )
    (net (code "31") (name "/Y_EN1") (class "Default")
      (node (ref "R140") (pin "2") (pinfunction "2_2") (pintype "passive"))
      (node (ref "R89") (pin "1") (pinfunction "1_1") (pintype "passive"))
      (node (ref "U6") (pin "2") (pinfunction "~{EN}_2") (pintype "input"))
    )
    (net (code "32") (name "/Y_STEP") (class "Default")
      (node (ref "R142") (pin "1") (pinfunction "1_1") (pintype "passive"))
    )
    (net (code "33") (name "/Y_STEP1") (class "Default")
      (node (ref "R142") (pin "2") (pinfunction "2_2") (pintype "passive"))
      (node (ref "U6") (pin "16") (pinfunction "STEP_16") (pintype "input"))
    )
    (net (code "34") (name "/Y_UART") (class "Default")
      (node (ref "R93") (pin "1") (pinfunction "1_1") (pintype "passive"))
      (node (ref "U6") (pin "14") (pinfunction "~{PD}_UART_14") (pintype "bidirectional"))
    )
    (net (code "35") (name "/ZDIAG") (class "Default")
      (node (ref "U7") (pin "11") (pinfunction "DIAG_11") (pintype "output"))
    )
    (net (code "36") (name "/Z_DIR") (class "Default")
      (node (ref "R154") (pin "1") (pinfunction "1_1") (pintype "passive"))
    )
    (net (code "37") (name "/Z_DIR1") (class "Default")
      (node (ref "R154") (pin "2") (pinfunction "2_2") (pintype "passive"))
      (node (ref "U7") (pin "19") (pinfunction "DIR_19") (pintype "input"))
    )
    (net (code "38") (name "/Z_EN") (class "Default")
      (node (ref "R150") (pin "1") (pinfunction "1_1") (pintype "passive"))
    )
    (net (code "39") (name "/Z_EN1") (class "Default")
      (node (ref "R150") (pin "2") (pinfunction "2_2") (pintype "passive"))
      (node (ref "R98") (pin "1") (pinfunction "1_1") (pintype "passive"))
      (node (ref "U7") (pin "2") (pinfunction "~{EN}_2") (pintype "input"))
    )
    (net (code "40") (name "/Z_STEP") (class "Default")
      (node (ref "R152") (pin "1") (pinfunction "1_1") (pintype "passive"))
    )
    (net (code "41") (name "/Z_STEP1") (class "Default")
      (node (ref "R152") (pin "2") (pinfunction "2_2") (pintype "passive"))
      (node (ref "U7") (pin "16") (pinfunction "STEP_16") (pintype "input"))
    )
    (net (code "42") (name "/Z_UART") (class "Default")
      (node (ref "R102") (pin "1") (pinfunction "1_1") (pintype "passive"))
      (node (ref "U7") (pin "14") (pinfunction "~{PD}_UART_14") (pintype "bidirectional"))
    )
    (net (code "43") (name "GND") (class "Default")
      (node (ref "C39") (pin "2") (pinfunction "2_2") (pintype "passive"))
      (node (ref "C40") (pin "2") (pinfunction "2_2") (pintype "passive"))
      (node (ref "C43") (pin "2") (pinfunction "2_2") (pintype "passive"))
      (node (ref "C44") (pin "2") (pinfunction "2_2") (pintype "passive"))
      (node (ref "C47") (pin "2") (pinfunction "2_2") (pintype "passive"))
      (node (ref "C48") (pin "2") (pinfunction "2_2") (pintype "passive"))
      (node (ref "C49") (pin "2") (pinfunction "2_2") (pintype "passive"))
      (node (ref "C50") (pin "2") (pinfunction "2_2") (pintype "passive"))
      (node (ref "C51") (pin "2") (pinfunction "2_2") (pintype "passive"))
      (node (ref "C52") (pin "2") (pinfunction "2_2") (pintype "passive"))
      (node (ref "C55") (pin "2") (pinfunction "2_2") (pintype "passive"))
      (node (ref "C56") (pin "2") (pinfunction "2_2") (pintype "passive"))
      (node (ref "C59") (pin "2") (pinfunction "2_2") (pintype "passive"))
      (node (ref "C60") (pin "2") (pinfunction "2_2") (pintype "passive"))
      (node (ref "C61") (pin "2") (pinfunction "2_2") (pintype "passive"))
      (node (ref "C62") (pin "2") (pinfunction "2_2") (pintype "passive"))
      (node (ref "C63") (pin "2") (pinfunction "2_2") (pintype "passive"))
      (node (ref "C66") (pin "2") (pinfunction "2_2") (pintype "passive"))
      (node (ref "C68") (pin "2") (pinfunction "2_2") (pintype "passive"))
      (node (ref "C69") (pin "2") (pinfunction "2_2") (pintype "passive"))
      (node (ref "R100") (pin "1") (pinfunction "1_1") (pintype "passive"))
      (node (ref "R101") (pin "1") (pinfunction "1_1") (pintype "passive"))
      (node (ref "R102") (pin "2") (pinfunction "2_2") (pintype "passive"))
      (node (ref "R103") (pin "2") (pinfunction "2_2") (pintype "passive"))
      (node (ref "R104") (pin "1") (pinfunction "1_1") (pintype "passive"))
      (node (ref "R105") (pin "1") (pinfunction "1_1") (pintype "passive"))
      (node (ref "R106") (pin "1") (pinfunction "1_1") (pintype "passive"))
      (node (ref "R107") (pin "1") (pinfunction "1_1") (pintype "passive"))
      (node (ref "R109") (pin "1") (pinfunction "1_1") (pintype "passive"))
      (node (ref "R110") (pin "2") (pinfunction "2_2") (pintype "passive"))
      (node (ref "R111") (pin "1") (pinfunction "1_1") (pintype "passive"))
      (node (ref "R112") (pin "1") (pinfunction "1_1") (pintype "passive"))
      (node (ref "R90") (pin "1") (pinfunction "1_1") (pintype "passive"))
      (node (ref "R91") (pin "1") (pinfunction "1_1") (pintype "passive"))
      (node (ref "R92") (pin "2") (pinfunction "2_2") (pintype "passive"))
      (node (ref "R93") (pin "2") (pinfunction "2_2") (pintype "passive"))
      (node (ref "R94") (pin "1") (pinfunction "1_1") (pintype "passive"))
      (node (ref "R95") (pin "1") (pinfunction "1_1") (pintype "passive"))
      (node (ref "R96") (pin "1") (pinfunction "1_1") (pintype "passive"))
      (node (ref "R97") (pin "1") (pinfunction "1_1") (pintype "passive"))
      (node (ref "U5") (pin "18") (pinfunction "GND_18") (pintype "power_in"))
      (node (ref "U5") (pin "29") (pinfunction "EXP_29") (pintype "power_in"))
      (node (ref "U5") (pin "3") (pinfunction "GND_3") (pintype "power_in"))
      (node (ref "U6") (pin "18") (pinfunction "GND_18") (pintype "power_in"))
      (node (ref "U6") (pin "29") (pinfunction "EXP_29") (pintype "power_in"))
      (node (ref "U6") (pin "3") (pinfunction "GND_3") (pintype "power_in"))
      (node (ref "U7") (pin "18") (pinfunction "GND_18") (pintype "power_in"))
      (node (ref "U7") (pin "29") (pinfunction "EXP_29") (pintype "power_in"))
      (node (ref "U7") (pin "3") (pinfunction "GND_3") (pintype "power_in"))
      (node (ref "U8") (pin "18") (pinfunction "GND_18") (pintype "power_in"))
      (node (ref "U8") (pin "29") (pinfunction "EXP_29") (pintype "power_in"))
      (node (ref "U8") (pin "3") (pinfunction "GND_3") (pintype "power_in"))
      (node (ref "U9") (pin "18") (pinfunction "GND_18") (pintype "power_in"))
      (node (ref "U9") (pin "29") (pinfunction "EXP_29") (pintype "power_in"))
      (node (ref "U9") (pin "3") (pinfunction "GND_3") (pintype "power_in"))
    )
    (net (code "44") (name "Net-(U5-5VOUT)") (class "Default")
      (node (ref "C39") (pin "1") (pinfunction "1_1") (pintype "passive"))
      (node (ref "U5") (pin "8") (pinfunction "5VOUT_8") (pintype "power_in"))
    )
    (net (code "45") (name "Net-(U5-BRA)") (class "Default")
      (node (ref "R95") (pin "2") (pinfunction "2_2") (pintype "passive"))
      (node (ref "U5") (pin "23") (pinfunction "BRA_23") (pintype "bidirectional"))
    )
    (net (code "46") (name "Net-(U5-BRB)") (class "Default")
      (node (ref "R94") (pin "2") (pinfunction "2_2") (pintype "passive"))
      (node (ref "U5") (pin "27") (pinfunction "BRB_27") (pintype "bidirectional"))
    )
    (net (code "47") (name "Net-(U5-CLK)") (class "Default")
      (node (ref "R90") (pin "2") (pinfunction "2_2") (pintype "passive"))
      (node (ref "U5") (pin "13") (pinfunction "CLK_13") (pintype "input"))
    )
    (net (code "48") (name "Net-(U5-CPI)") (class "Default")
      (node (ref "C45") (pin "2") (pinfunction "2_2") (pintype "passive"))
      (node (ref "U5") (pin "5") (pinfunction "CPI_5") (pintype "input"))
    )
    (net (code "49") (name "Net-(U5-CPO)") (class "Default")
      (node (ref "C45") (pin "1") (pinfunction "1_1") (pintype "passive"))
      (node (ref "U5") (pin "4") (pinfunction "CPO_4") (pintype "output"))
    )
    (net (code "50") (name "Net-(U5-OA1)") (class "Default")
      (node (ref "J42") (pin "2") (pinfunction "2_2") (pintype "passive"))
      (node (ref "U5") (pin "24") (pinfunction "OA1_24") (pintype "output"))
    )
    (net (code "51") (name "Net-(U5-OA2)") (class "Default")
      (node (ref "J42") (pin "1") (pinfunction "1_1") (pintype "passive"))
      (node (ref "U5") (pin "21") (pinfunction "OA2_21") (pintype "output"))
    )
    (net (code "52") (name "Net-(U5-OB1)") (class "Default")
      (node (ref "J42") (pin "3") (pinfunction "3_3") (pintype "passive"))
      (node (ref "U5") (pin "26") (pinfunction "OB1_26") (pintype "output"))
    )
    (net (code "53") (name "Net-(U5-OB2)") (class "Default")
      (node (ref "J42") (pin "4") (pinfunction "4_4") (pintype "passive"))
      (node (ref "U5") (pin "1") (pinfunction "OB2_1") (pintype "output"))
    )
    (net (code "54") (name "Net-(U5-VCP)") (class "Default")
      (node (ref "C41") (pin "1") (pinfunction "1_1") (pintype "passive"))
      (node (ref "U5") (pin "6") (pinfunction "VCP_6") (pintype "power_in"))
    )
    (net (code "55") (name "Net-(U6-5VOUT)") (class "Default")
      (node (ref "C40") (pin "1") (pinfunction "1_1") (pintype "passive"))
      (node (ref "U6") (pin "8") (pinfunction "5VOUT_8") (pintype "power_in"))
    )
    (net (code "56") (name "Net-(U6-BRA)") (class "Default")
      (node (ref "R97") (pin "2") (pinfunction "2_2") (pintype "passive"))
      (node (ref "U6") (pin "23") (pinfunction "BRA_23") (pintype "bidirectional"))
    )
    (net (code "57") (name "Net-(U6-BRB)") (class "Default")
      (node (ref "R96") (pin "2") (pinfunction "2_2") (pintype "passive"))
      (node (ref "U6") (pin "27") (pinfunction "BRB_27") (pintype "bidirectional"))
    )
    (net (code "58") (name "Net-(U6-CLK)") (class "Default")
      (node (ref "R91") (pin "2") (pinfunction "2_2") (pintype "passive"))
      (node (ref "U6") (pin "13") (pinfunction "CLK_13") (pintype "input"))
    )
    (net (code "59") (name "Net-(U6-CPI)") (class "Default")
      (node (ref "C46") (pin "2") (pinfunction "2_2") (pintype "passive"))
      (node (ref "U6") (pin "5") (pinfunction "CPI_5") (pintype "input"))
    )
    (net (code "60") (name "Net-(U6-CPO)") (class "Default")
      (node (ref "C46") (pin "1") (pinfunction "1_1") (pintype "passive"))
      (node (ref "U6") (pin "4") (pinfunction "CPO_4") (pintype "output"))
    )
    (net (code "61") (name "Net-(U6-OA1)") (class "Default")
      (node (ref "J43") (pin "2") (pinfunction "2_2") (pintype "passive"))
      (node (ref "U6") (pin "24") (pinfunction "OA1_24") (pintype "output"))
    )
    (net (code "62") (name "Net-(U6-OA2)") (class "Default")
      (node (ref "J43") (pin "1") (pinfunction "1_1") (pintype "passive"))
      (node (ref "U6") (pin "21") (pinfunction "OA2_21") (pintype "output"))
    )
    (net (code "63") (name "Net-(U6-OB1)") (class "Default")
      (node (ref "J43") (pin "3") (pinfunction "3_3") (pintype "passive"))
      (node (ref "U6") (pin "26") (pinfunction "OB1_26") (pintype "output"))
    )
    (net (code "64") (name "Net-(U6-OB2)") (class "Default")
      (node (ref "J43") (pin "4") (pinfunction "4_4") (pintype "passive"))
      (node (ref "U6") (pin "1") (pinfunction "OB2_1") (pintype "output"))
    )
    (net (code "65") (name "Net-(U6-VCP)") (class "Default")
      (node (ref "C42") (pin "1") (pinfunction "1_1") (pintype "passive"))
      (node (ref "U6") (pin "6") (pinfunction "VCP_6") (pintype "power_in"))
    )
    (net (code "66") (name "Net-(U7-5VOUT)") (class "Default")
      (node (ref "C51") (pin "1") (pinfunction "1_1") (pintype "passive"))
      (node (ref "U7") (pin "8") (pinfunction "5VOUT_8") (pintype "power_in"))
    )
    (net (code "67") (name "Net-(U7-BRA)") (class "Default")
      (node (ref "R105") (pin "2") (pinfunction "2_2") (pintype "passive"))
      (node (ref "U7") (pin "23") (pinfunction "BRA_23") (pintype "bidirectional"))
    )
    (net (code "68") (name "Net-(U7-BRB)") (class "Default")
      (node (ref "R104") (pin "2") (pinfunction "2_2") (pintype "passive"))
      (node (ref "U7") (pin "27") (pinfunction "BRB_27") (pintype "bidirectional"))
    )
    (net (code "69") (name "Net-(U7-CLK)") (class "Default")
      (node (ref "R100") (pin "2") (pinfunction "2_2") (pintype "passive"))
      (node (ref "U7") (pin "13") (pinfunction "CLK_13") (pintype "input"))
    )
    (net (code "70") (name "Net-(U7-CPI)") (class "Default")
      (node (ref "C57") (pin "2") (pinfunction "2_2") (pintype "passive"))
      (node (ref "U7") (pin "5") (pinfunction "CPI_5") (pintype "input"))
    )
    (net (code "71") (name "Net-(U7-CPO)") (class "Default")
      (node (ref "C57") (pin "1") (pinfunction "1_1") (pintype "passive"))
      (node (ref "U7") (pin "4") (pinfunction "CPO_4") (pintype "output"))
    )
    (net (code "72") (name "Net-(U7-OA1)") (class "Default")
      (node (ref "J44") (pin "2") (pinfunction "2_2") (pintype "passive"))
      (node (ref "U7") (pin "24") (pinfunction "OA1_24") (pintype "output"))
    )
    (net (code "73") (name "Net-(U7-OA2)") (class "Default")
      (node (ref "J44") (pin "1") (pinfunction "1_1") (pintype "passive"))
      (node (ref "U7") (pin "21") (pinfunction "OA2_21") (pintype "output"))
    )
    (net (code "74") (name "Net-(U7-OB1)") (class "Default")
      (node (ref "J44") (pin "3") (pinfunction "3_3") (pintype "passive"))
      (node (ref "U7") (pin "26") (pinfunction "OB1_26") (pintype "output"))
    )
    (net (code "75") (name "Net-(U7-OB2)") (class "Default")
      (node (ref "J44") (pin "4") (pinfunction "4_4") (pintype "passive"))
      (node (ref "U7") (pin "1") (pinfunction "OB2_1") (pintype "output"))
    )
    (net (code "76") (name "Net-(U7-VCP)") (class "Default")
      (node (ref "C53") (pin "1") (pinfunction "1_1") (pintype "passive"))
      (node (ref "U7") (pin "6") (pinfunction "VCP_6") (pintype "power_in"))
    )
    (net (code "77") (name "Net-(U8-5VOUT)") (class "Default")
      (node (ref "C52") (pin "1") (pinfunction "1_1") (pintype "passive"))
      (node (ref "U8") (pin "8") (pinfunction "5VOUT_8") (pintype "power_in"))
    )
    (net (code "78") (name "Net-(U8-BRA)") (class "Default")
      (node (ref "R107") (pin "2") (pinfunction "2_2") (pintype "passive"))
      (node (ref "U8") (pin "23") (pinfunction "BRA_23") (pintype "bidirectional"))
    )
    (net (code "79") (name "Net-(U8-BRB)") (class "Default")
      (node (ref "R106") (pin "2") (pinfunction "2_2") (pintype "passive"))
      (node (ref "U8") (pin "27") (pinfunction "BRB_27") (pintype "bidirectional"))
    )
    (net (code "80") (name "Net-(U8-CLK)") (class "Default")
      (node (ref "R101") (pin "2") (pinfunction "2_2") (pintype "passive"))
      (node (ref "U8") (pin "13") (pinfunction "CLK_13") (pintype "input"))
    )
    (net (code "81") (name "Net-(U8-CPI)") (class "Default")
      (node (ref "C58") (pin "2") (pinfunction "2_2") (pintype "passive"))
      (node (ref "U8") (pin "5") (pinfunction "CPI_5") (pintype "input"))
    )
    (net (code "82") (name "Net-(U8-CPO)") (class "Default")
      (node (ref "C58") (pin "1") (pinfunction "1_1") (pintype "passive"))
      (node (ref "U8") (pin "4") (pinfunction "CPO_4") (pintype "output"))
    )
    (net (code "83") (name "Net-(U8-OA1)") (class "Default")
      (node (ref "J45") (pin "2") (pinfunction "2_2") (pintype "passive"))
      (node (ref "U8") (pin "24") (pinfunction "OA1_24") (pintype "output"))
    )
    (net (code "84") (name "Net-(U8-OA2)") (class "Default")
      (node (ref "J45") (pin "1") (pinfunction "1_1") (pintype "passive"))
      (node (ref "U8") (pin "21") (pinfunction "OA2_21") (pintype "output"))
    )
    (net (code "85") (name "Net-(U8-OB1)") (class "Default")
      (node (ref "J45") (pin "3") (pinfunction "3_3") (pintype "passive"))
      (node (ref "U8") (pin "26") (pinfunction "OB1_26") (pintype "output"))
    )
    (net (code "86") (name "Net-(U8-OB2)") (class "Default")
      (node (ref "J45") (pin "4") (pinfunction "4_4") (pintype "passive"))
      (node (ref "U8") (pin "1") (pinfunction "OB2_1") (pintype "output"))
    )
    (net (code "87") (name "Net-(U8-VCP)") (class "Default")
      (node (ref "C54") (pin "1") (pinfunction "1_1") (pintype "passive"))
      (node (ref "U8") (pin "6") (pinfunction "VCP_6") (pintype "power_in"))
    )
    (net (code "88") (name "Net-(U9-5VOUT)") (class "Default")
      (node (ref "C63") (pin "1") (pinfunction "1_1") (pintype "passive"))
      (node (ref "U9") (pin "8") (pinfunction "5VOUT_8") (pintype "power_in"))
    )
    (net (code "89") (name "Net-(U9-BRA)") (class "Default")
      (node (ref "R112") (pin "2") (pinfunction "2_2") (pintype "passive"))
      (node (ref "U9") (pin "23") (pinfunction "BRA_23") (pintype "bidirectional"))
    )
    (net (code "90") (name "Net-(U9-BRB)") (class "Default")
      (node (ref "R111") (pin "2") (pinfunction "2_2") (pintype "passive"))
      (node (ref "U9") (pin "27") (pinfunction "BRB_27") (pintype "bidirectional"))
    )
    (net (code "91") (name "Net-(U9-CLK)") (class "Default")
      (node (ref "R109") (pin "2") (pinfunction "2_2") (pintype "passive"))
      (node (ref "U9") (pin "13") (pinfunction "CLK_13") (pintype "input"))
    )
    (net (code "92") (name "Net-(U9-CPI)") (class "Default")
      (node (ref "C67") (pin "2") (pinfunction "2_2") (pintype "passive"))
      (node (ref "U9") (pin "5") (pinfunction "CPI_5") (pintype "input"))
    )
    (net (code "93") (name "Net-(U9-CPO)") (class "Default")
      (node (ref "C67") (pin "1") (pinfunction "1_1") (pintype "passive"))
      (node (ref "U9") (pin "4") (pinfunction "CPO_4") (pintype "output"))
    )
    (net (code "94") (name "Net-(U9-OA1)") (class "Default")
      (node (ref "J46") (pin "2") (pinfunction "2_2") (pintype "passive"))
      (node (ref "U9") (pin "24") (pinfunction "OA1_24") (pintype "output"))
    )
    (net (code "95") (name "Net-(U9-OA2)") (class "Default")
      (node (ref "J46") (pin "1") (pinfunction "1_1") (pintype "passive"))
      (node (ref "U9") (pin "21") (pinfunction "OA2_21") (pintype "output"))
    )
    (net (code "96") (name "Net-(U9-OB1)") (class "Default")
      (node (ref "J46") (pin "3") (pinfunction "3_3") (pintype "passive"))
      (node (ref "U9") (pin "26") (pinfunction "OB1_26") (pintype "output"))
    )
    (net (code "97") (name "Net-(U9-OB2)") (class "Default")
      (node (ref "J46") (pin "4") (pinfunction "4_4") (pintype "passive"))
      (node (ref "U9") (pin "1") (pinfunction "OB2_1") (pintype "output"))
    )
    (net (code "98") (name "Net-(U9-VCP)") (class "Default")
      (node (ref "C65") (pin "1") (pinfunction "1_1") (pintype "passive"))
      (node (ref "U9") (pin "6") (pinfunction "VCP_6") (pintype "power_in"))
    )
    (net (code "99") (name "unconnected-(U5-INDEX-Pad12)") (class "Default")
      (node (ref "U5") (pin "12") (pinfunction "INDEX_12") (pintype "output+no_connect"))
    )
    (net (code "100") (name "unconnected-(U5-MS1_AD0-Pad9)") (class "Default")
      (node (ref "U5") (pin "9") (pinfunction "MS1_AD0_9") (pintype "input+no_connect"))
    )
    (net (code "101") (name "unconnected-(U5-MS2_AD1-Pad10)") (class "Default")
      (node (ref "U5") (pin "10") (pinfunction "MS2_AD1_10") (pintype "input+no_connect"))
    )
    (net (code "102") (name "unconnected-(U5-NC-Pad25)") (class "Default")
      (node (ref "U5") (pin "25") (pinfunction "NC_25") (pintype "passive+no_connect"))
    )
    (net (code "103") (name "unconnected-(U5-SPREAD-Pad7)") (class "Default")
      (node (ref "U5") (pin "7") (pinfunction "SPREAD_7") (pintype "input+no_connect"))
    )
    (net (code "104") (name "unconnected-(U5-STDBY-Pad20)") (class "Default")
      (node (ref "U5") (pin "20") (pinfunction "STDBY_20") (pintype "input+no_connect"))
    )
    (net (code "105") (name "unconnected-(U5-VREF-Pad17)") (class "Default")
      (node (ref "U5") (pin "17") (pinfunction "VREF_17") (pintype "input+no_connect"))
    )
    (net (code "106") (name "unconnected-(U6-INDEX-Pad12)") (class "Default")
      (node (ref "U6") (pin "12") (pinfunction "INDEX_12") (pintype "output+no_connect"))
    )
    (net (code "107") (name "unconnected-(U6-MS1_AD0-Pad9)") (class "Default")
      (node (ref "U6") (pin "9") (pinfunction "MS1_AD0_9") (pintype "input+no_connect"))
    )
    (net (code "108") (name "unconnected-(U6-MS2_AD1-Pad10)") (class "Default")
      (node (ref "U6") (pin "10") (pinfunction "MS2_AD1_10") (pintype "input+no_connect"))
    )
    (net (code "109") (name "unconnected-(U6-NC-Pad25)") (class "Default")
      (node (ref "U6") (pin "25") (pinfunction "NC_25") (pintype "passive+no_connect"))
    )
    (net (code "110") (name "unconnected-(U6-SPREAD-Pad7)") (class "Default")
      (node (ref "U6") (pin "7") (pinfunction "SPREAD_7") (pintype "input+no_connect"))
    )
    (net (code "111") (name "unconnected-(U6-STDBY-Pad20)") (class "Default")
      (node (ref "U6") (pin "20") (pinfunction "STDBY_20") (pintype "input+no_connect"))
    )
    (net (code "112") (name "unconnected-(U6-VREF-Pad17)") (class "Default")
      (node (ref "U6") (pin "17") (pinfunction "VREF_17") (pintype "input+no_connect"))
    )
    (net (code "113") (name "unconnected-(U7-INDEX-Pad12)") (class "Default")
      (node (ref "U7") (pin "12") (pinfunction "INDEX_12") (pintype "output+no_connect"))
    )
    (net (code "114") (name "unconnected-(U7-MS1_AD0-Pad9)") (class "Default")
      (node (ref "U7") (pin "9") (pinfunction "MS1_AD0_9") (pintype "input+no_connect"))
    )
    (net (code "115") (name "unconnected-(U7-MS2_AD1-Pad10)") (class "Default")
      (node (ref "U7") (pin "10") (pinfunction "MS2_AD1_10") (pintype "input+no_connect"))
    )
    (net (code "116") (name "unconnected-(U7-NC-Pad25)") (class "Default")
      (node (ref "U7") (pin "25") (pinfunction "NC_25") (pintype "passive+no_connect"))
    )
    (net (code "117") (name "unconnected-(U7-SPREAD-Pad7)") (class "Default")
      (node (ref "U7") (pin "7") (pinfunction "SPREAD_7") (pintype "input+no_connect"))
    )
    (net (code "118") (name "unconnected-(U7-STDBY-Pad20)") (class "Default")
      (node (ref "U7") (pin "20") (pinfunction "STDBY_20") (pintype "input+no_connect"))
    )
    (net (code "119") (name "unconnected-(U7-VREF-Pad17)") (class "Default")
      (node (ref "U7") (pin "17") (pinfunction "VREF_17") (pintype "input+no_connect"))
    )
    (net (code "120") (name "unconnected-(U8-INDEX-Pad12)") (class "Default")
      (node (ref "U8") (pin "12") (pinfunction "INDEX_12") (pintype "output+no_connect"))
    )
    (net (code "121") (name "unconnected-(U8-MS1_AD0-Pad9)") (class "Default")
      (node (ref "U8") (pin "9") (pinfunction "MS1_AD0_9") (pintype "input+no_connect"))
    )
    (net (code "122") (name "unconnected-(U8-MS2_AD1-Pad10)") (class "Default")
      (node (ref "U8") (pin "10") (pinfunction "MS2_AD1_10") (pintype "input+no_connect"))
    )
    (net (code "123") (name "unconnected-(U8-NC-Pad25)") (class "Default")
      (node (ref "U8") (pin "25") (pinfunction "NC_25") (pintype "passive+no_connect"))
    )
    (net (code "124") (name "unconnected-(U8-SPREAD-Pad7)") (class "Default")
      (node (ref "U8") (pin "7") (pinfunction "SPREAD_7") (pintype "input+no_connect"))
    )
    (net (code "125") (name "unconnected-(U8-STDBY-Pad20)") (class "Default")
      (node (ref "U8") (pin "20") (pinfunction "STDBY_20") (pintype "input+no_connect"))
    )
    (net (code "126") (name "unconnected-(U8-VREF-Pad17)") (class "Default")
      (node (ref "U8") (pin "17") (pinfunction "VREF_17") (pintype "input+no_connect"))
    )
    (net (code "127") (name "unconnected-(U9-INDEX-Pad12)") (class "Default")
      (node (ref "U9") (pin "12") (pinfunction "INDEX_12") (pintype "output+no_connect"))
    )
    (net (code "128") (name "unconnected-(U9-MS1_AD0-Pad9)") (class "Default")
      (node (ref "U9") (pin "9") (pinfunction "MS1_AD0_9") (pintype "input+no_connect"))
    )
    (net (code "129") (name "unconnected-(U9-MS2_AD1-Pad10)") (class "Default")
      (node (ref "U9") (pin "10") (pinfunction "MS2_AD1_10") (pintype "input+no_connect"))
    )
    (net (code "130") (name "unconnected-(U9-NC-Pad25)") (class "Default")
      (node (ref "U9") (pin "25") (pinfunction "NC_25") (pintype "passive+no_connect"))
    )
    (net (code "131") (name "unconnected-(U9-SPREAD-Pad7)") (class "Default")
      (node (ref "U9") (pin "7") (pinfunction "SPREAD_7") (pintype "input+no_connect"))
    )
    (net (code "132") (name "unconnected-(U9-STDBY-Pad20)") (class "Default")
      (node (ref "U9") (pin "20") (pinfunction "STDBY_20") (pintype "input+no_connect"))
    )
    (net (code "133") (name "unconnected-(U9-VREF-Pad17)") (class "Default")
      (node (ref "U9") (pin "17") (pinfunction "VREF_17") (pintype "input+no_connect"))
    )
  )
)
